# INC-FBTMC429-V1.net
KiCad netlist of a schematic drawn in Altium Designer
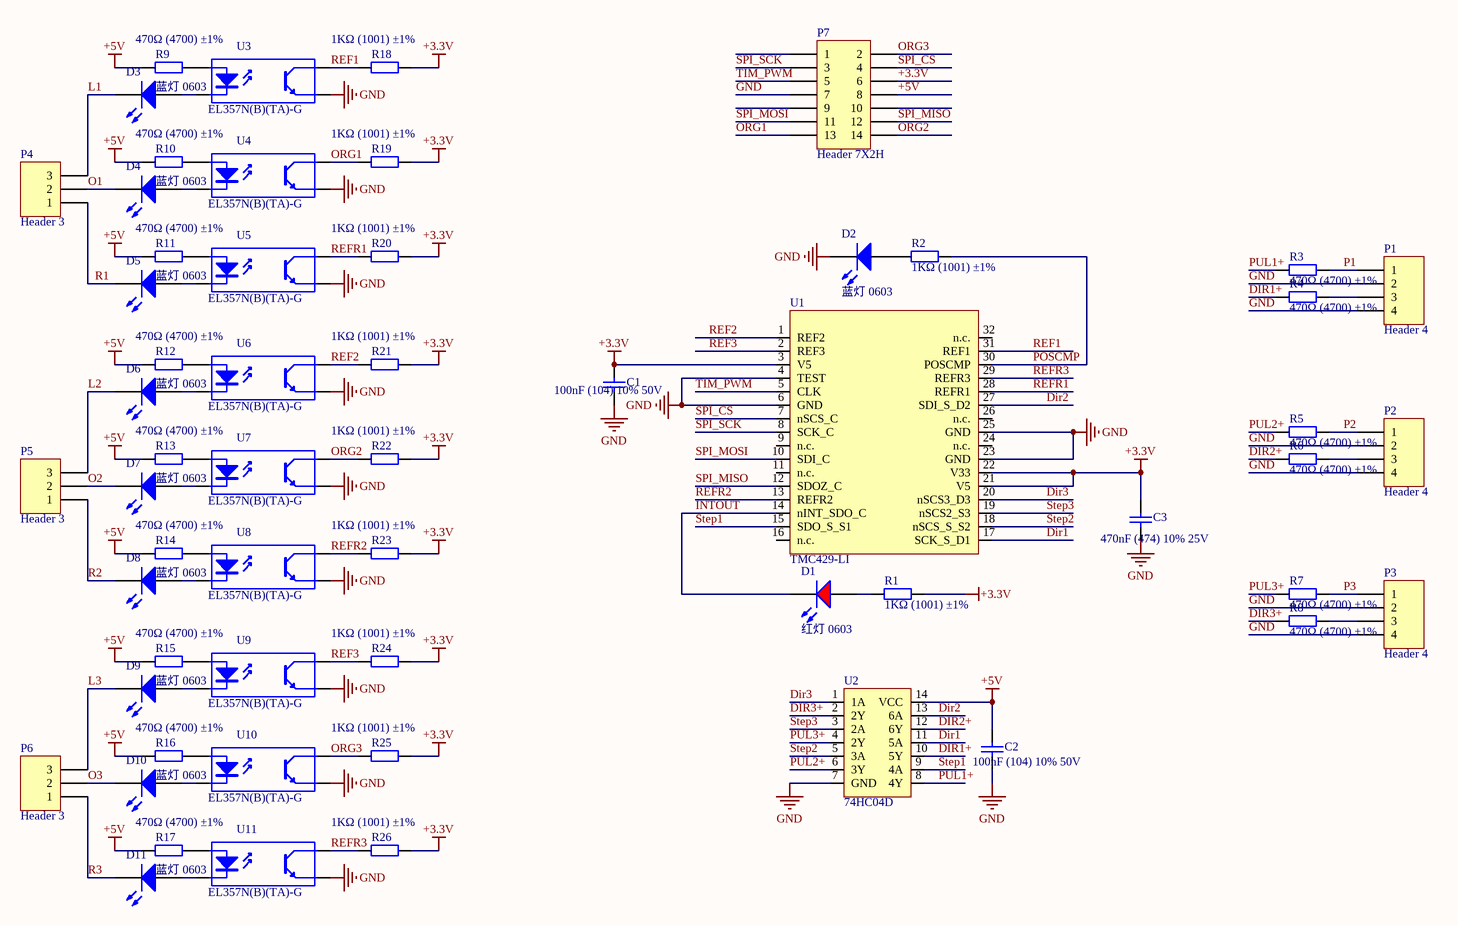
[diagram p0: INC-FBTMC429-V1.SchDoc]

(export (version "E")
  (design (tool "Eeschema 10.0.6"))
  (components
    (comp (ref "C1")
      (value "100nF (104) 10% 50V")
      (footprint "0603_C")
      (description "贴片电容")
      (libsource (lib "Miscellaneous Devices LC") (part "0603 100nF (104) 10% 50V"))
    )
    (comp (ref "C2")
      (value "100nF (104) 10% 50V")
      (footprint "0603_C")
      (description "贴片电容")
      (libsource (lib "Miscellaneous Devices LC") (part "0603 100nF (104) 10% 50V"))
    )
    (comp (ref "C3")
      (value "470nF (474) 10% 25V")
      (footprint "0603_C")
      (description "贴片电容")
      (libsource (lib "Miscellaneous Devices LC") (part "0603 470nF (474) 10% 25V"))
    )
    (comp (ref "D1")
      (value "红灯 0603")
      (footprint "0603_LED_S1")
      (description "发光二极管")
      (libsource (lib "Miscellaneous Devices LC") (part "0603 红灯"))
    )
    (comp (ref "D2")
      (value "蓝灯 0603")
      (footprint "0603_LED_S1")
      (description "发光二极管")
      (libsource (lib "Miscellaneous Devices LC") (part "0603 蓝灯"))
    )
    (comp (ref "D3")
      (value "蓝灯 0603")
      (footprint "0603_LED_S1")
      (description "发光二极管")
      (libsource (lib "Miscellaneous Devices LC") (part "0603 蓝灯"))
    )
    (comp (ref "D4")
      (value "蓝灯 0603")
      (footprint "0603_LED_S1")
      (description "发光二极管")
      (libsource (lib "Miscellaneous Devices LC") (part "0603 蓝灯"))
    )
    (comp (ref "D5")
      (value "蓝灯 0603")
      (footprint "0603_LED_S1")
      (description "发光二极管")
      (libsource (lib "Miscellaneous Devices LC") (part "0603 蓝灯"))
    )
    (comp (ref "D6")
      (value "蓝灯 0603")
      (footprint "0603_LED_S1")
      (description "发光二极管")
      (libsource (lib "Miscellaneous Devices LC") (part "0603 蓝灯"))
    )
    (comp (ref "D7")
      (value "蓝灯 0603")
      (footprint "0603_LED_S1")
      (description "发光二极管")
      (libsource (lib "Miscellaneous Devices LC") (part "0603 蓝灯"))
    )
    (comp (ref "D8")
      (value "蓝灯 0603")
      (footprint "0603_LED_S1")
      (description "发光二极管")
      (libsource (lib "Miscellaneous Devices LC") (part "0603 蓝灯"))
    )
    (comp (ref "D9")
      (value "蓝灯 0603")
      (footprint "0603_LED_S1")
      (description "发光二极管")
      (libsource (lib "Miscellaneous Devices LC") (part "0603 蓝灯"))
    )
    (comp (ref "D10")
      (value "蓝灯 0603")
      (footprint "0603_LED_S1")
      (description "发光二极管")
      (libsource (lib "Miscellaneous Devices LC") (part "0603 蓝灯"))
    )
    (comp (ref "D11")
      (value "蓝灯 0603")
      (footprint "0603_LED_S1")
      (description "发光二极管")
      (libsource (lib "Miscellaneous Devices LC") (part "0603 蓝灯"))
    )
    (comp (ref "P1")
      (value "Header 4")
      (footprint "WJ15EDGVC-3.81-4P")
      (description "Header, 4-Pin")
      (fields (field (name "PUBLISHER") "Altium Limited"))
      (libsource (lib "Miscellaneous Connectors") (part "Header 4"))
    )
    (comp (ref "P2")
      (value "Header 4")
      (footprint "WJ15EDGVC-3.81-4P")
      (description "Header, 4-Pin")
      (fields (field (name "PUBLISHER") "Altium Limited"))
      (libsource (lib "Miscellaneous Connectors") (part "Header 4"))
    )
    (comp (ref "P3")
      (value "Header 4")
      (footprint "WJ15EDGVC-3.81-4P")
      (description "Header, 4-Pin")
      (fields (field (name "PUBLISHER") "Altium Limited"))
      (libsource (lib "Miscellaneous Connectors") (part "Header 4"))
    )
    (comp (ref "P4")
      (value "Header 3")
      (footprint "WJ15EDGVC-3.81-3P")
      (description "Header, 3-Pin")
      (fields (field (name "PUBLISHER") "Altium Limited"))
      (libsource (lib "Miscellaneous Connectors") (part "Header 3"))
    )
    (comp (ref "P5")
      (value "Header 3")
      (footprint "WJ15EDGVC-3.81-3P")
      (description "Header, 3-Pin")
      (fields (field (name "PUBLISHER") "Altium Limited"))
      (libsource (lib "Miscellaneous Connectors") (part "Header 3"))
    )
    (comp (ref "P6")
      (value "Header 3")
      (footprint "WJ15EDGVC-3.81-3P")
      (description "Header, 3-Pin")
      (fields (field (name "PUBLISHER") "Altium Limited"))
      (libsource (lib "Miscellaneous Connectors") (part "Header 3"))
    )
    (comp (ref "P7")
      (value "Header 7X2H")
      (footprint "直牛角连接器 2*7*2.54")
      (description "Header, 7-Pin, Dual row, Right Angle")
      (fields (field (name "PUBLISHER") "Altium Limited"))
      (libsource (lib "Miscellaneous Connectors") (part "Header 7X2H"))
    )
    (comp (ref "R1")
      (value "1KΩ (1001) ±1%")
      (footprint "0603_R")
      (description "贴片电阻")
      (libsource (lib "") (part "0603 1KΩ (1001) 1%_1"))
    )
    (comp (ref "R2")
      (value "1KΩ (1001) ±1%")
      (footprint "0603_R")
      (description "贴片电阻")
      (libsource (lib "") (part "0603 1KΩ (1001) 1%_1"))
    )
    (comp (ref "R3")
      (value "470Ω (4700) ±1%")
      (footprint "0603_R")
      (description "贴片电阻")
      (libsource (lib "Miscellaneous Devices LC") (part "0603 470Ω (4700) 1%"))
    )
    (comp (ref "R4")
      (value "470Ω (4700) ±1%")
      (footprint "0603_R")
      (description "贴片电阻")
      (libsource (lib "Miscellaneous Devices LC") (part "0603 470Ω (4700) 1%"))
    )
    (comp (ref "R5")
      (value "470Ω (4700) ±1%")
      (footprint "0603_R")
      (description "贴片电阻")
      (libsource (lib "Miscellaneous Devices LC") (part "0603 470Ω (4700) 1%"))
    )
    (comp (ref "R6")
      (value "470Ω (4700) ±1%")
      (footprint "0603_R")
      (description "贴片电阻")
      (libsource (lib "Miscellaneous Devices LC") (part "0603 470Ω (4700) 1%"))
    )
    (comp (ref "R7")
      (value "470Ω (4700) ±1%")
      (footprint "0603_R")
      (description "贴片电阻")
      (libsource (lib "Miscellaneous Devices LC") (part "0603 470Ω (4700) 1%"))
    )
    (comp (ref "R8")
      (value "470Ω (4700) ±1%")
      (footprint "0603_R")
      (description "贴片电阻")
      (libsource (lib "Miscellaneous Devices LC") (part "0603 470Ω (4700) 1%"))
    )
    (comp (ref "R9")
      (value "470Ω (4700) ±1%")
      (footprint "0603_R")
      (description "贴片电阻")
      (libsource (lib "Miscellaneous Devices LC") (part "0603 470Ω (4700) 1%"))
    )
    (comp (ref "R10")
      (value "470Ω (4700) ±1%")
      (footprint "0603_R")
      (description "贴片电阻")
      (libsource (lib "Miscellaneous Devices LC") (part "0603 470Ω (4700) 1%"))
    )
    (comp (ref "R11")
      (value "470Ω (4700) ±1%")
      (footprint "0603_R")
      (description "贴片电阻")
      (libsource (lib "Miscellaneous Devices LC") (part "0603 470Ω (4700) 1%"))
    )
    (comp (ref "R12")
      (value "470Ω (4700) ±1%")
      (footprint "0603_R")
      (description "贴片电阻")
      (libsource (lib "Miscellaneous Devices LC") (part "0603 470Ω (4700) 1%"))
    )
    (comp (ref "R13")
      (value "470Ω (4700) ±1%")
      (footprint "0603_R")
      (description "贴片电阻")
      (libsource (lib "Miscellaneous Devices LC") (part "0603 470Ω (4700) 1%"))
    )
    (comp (ref "R14")
      (value "470Ω (4700) ±1%")
      (footprint "0603_R")
      (description "贴片电阻")
      (libsource (lib "Miscellaneous Devices LC") (part "0603 470Ω (4700) 1%"))
    )
    (comp (ref "R15")
      (value "470Ω (4700) ±1%")
      (footprint "0603_R")
      (description "贴片电阻")
      (libsource (lib "Miscellaneous Devices LC") (part "0603 470Ω (4700) 1%"))
    )
    (comp (ref "R16")
      (value "470Ω (4700) ±1%")
      (footprint "0603_R")
      (description "贴片电阻")
      (libsource (lib "Miscellaneous Devices LC") (part "0603 470Ω (4700) 1%"))
    )
    (comp (ref "R17")
      (value "470Ω (4700) ±1%")
      (footprint "0603_R")
      (description "贴片电阻")
      (libsource (lib "Miscellaneous Devices LC") (part "0603 470Ω (4700) 1%"))
    )
    (comp (ref "R18")
      (value "1KΩ (1001) ±1%")
      (footprint "0603_R")
      (description "贴片电阻")
      (libsource (lib "Miscellaneous Devices LC") (part "0603 1KΩ (1001) 1%"))
    )
    (comp (ref "R19")
      (value "1KΩ (1001) ±1%")
      (footprint "0603_R")
      (description "贴片电阻")
      (libsource (lib "Miscellaneous Devices LC") (part "0603 1KΩ (1001) 1%"))
    )
    (comp (ref "R20")
      (value "1KΩ (1001) ±1%")
      (footprint "0603_R")
      (description "贴片电阻")
      (libsource (lib "Miscellaneous Devices LC") (part "0603 1KΩ (1001) 1%"))
    )
    (comp (ref "R21")
      (value "1KΩ (1001) ±1%")
      (footprint "0603_R")
      (description "贴片电阻")
      (libsource (lib "Miscellaneous Devices LC") (part "0603 1KΩ (1001) 1%"))
    )
    (comp (ref "R22")
      (value "1KΩ (1001) ±1%")
      (footprint "0603_R")
      (description "贴片电阻")
      (libsource (lib "Miscellaneous Devices LC") (part "0603 1KΩ (1001) 1%"))
    )
    (comp (ref "R23")
      (value "1KΩ (1001) ±1%")
      (footprint "0603_R")
      (description "贴片电阻")
      (libsource (lib "Miscellaneous Devices LC") (part "0603 1KΩ (1001) 1%"))
    )
    (comp (ref "R24")
      (value "1KΩ (1001) ±1%")
      (footprint "0603_R")
      (description "贴片电阻")
      (libsource (lib "Miscellaneous Devices LC") (part "0603 1KΩ (1001) 1%"))
    )
    (comp (ref "R25")
      (value "1KΩ (1001) ±1%")
      (footprint "0603_R")
      (description "贴片电阻")
      (libsource (lib "Miscellaneous Devices LC") (part "0603 1KΩ (1001) 1%"))
    )
    (comp (ref "R26")
      (value "1KΩ (1001) ±1%")
      (footprint "0603_R")
      (description "贴片电阻")
      (libsource (lib "Miscellaneous Devices LC") (part "0603 1KΩ (1001) 1%"))
    )
    (comp (ref "U1")
      (value "TMC429-LI")
      (footprint "QFN-32_5x5x05P")
      (libsource (lib "GB-SCH") (part "TMC429-LI"))
    )
    (comp (ref "U2")
      (value "74HC04D")
      (footprint "SOIC-14_150mil")
      (libsource (lib "GB-SCH") (part "74HC04"))
    )
    (comp (ref "U3")
      (value "EL357N(B)(TA)-G")
      (footprint "SOP-4_P2.54")
      (description "贴片光耦")
      (libsource (lib "Miscellaneous Devices LC") (part "EL357N(B)(TA)-G"))
    )
    (comp (ref "U4")
      (value "EL357N(B)(TA)-G")
      (footprint "SOP-4_P2.54")
      (description "贴片光耦")
      (libsource (lib "Miscellaneous Devices LC") (part "EL357N(B)(TA)-G"))
    )
    (comp (ref "U5")
      (value "EL357N(B)(TA)-G")
      (footprint "SOP-4_P2.54")
      (description "贴片光耦")
      (libsource (lib "Miscellaneous Devices LC") (part "EL357N(B)(TA)-G"))
    )
    (comp (ref "U6")
      (value "EL357N(B)(TA)-G")
      (footprint "SOP-4_P2.54")
      (description "贴片光耦")
      (libsource (lib "Miscellaneous Devices LC") (part "EL357N(B)(TA)-G"))
    )
    (comp (ref "U7")
      (value "EL357N(B)(TA)-G")
      (footprint "SOP-4_P2.54")
      (description "贴片光耦")
      (libsource (lib "Miscellaneous Devices LC") (part "EL357N(B)(TA)-G"))
    )
    (comp (ref "U8")
      (value "EL357N(B)(TA)-G")
      (footprint "SOP-4_P2.54")
      (description "贴片光耦")
      (libsource (lib "Miscellaneous Devices LC") (part "EL357N(B)(TA)-G"))
    )
    (comp (ref "U9")
      (value "EL357N(B)(TA)-G")
      (footprint "SOP-4_P2.54")
      (description "贴片光耦")
      (libsource (lib "Miscellaneous Devices LC") (part "EL357N(B)(TA)-G"))
    )
    (comp (ref "U10")
      (value "EL357N(B)(TA)-G")
      (footprint "SOP-4_P2.54")
      (description "贴片光耦")
      (libsource (lib "Miscellaneous Devices LC") (part "EL357N(B)(TA)-G"))
    )
    (comp (ref "U11")
      (value "EL357N(B)(TA)-G")
      (footprint "SOP-4_P2.54")
      (description "贴片光耦")
      (libsource (lib "Miscellaneous Devices LC") (part "EL357N(B)(TA)-G"))
    )
  )
  (nets
    (net (code "1") (name "+3.3V") (class "Default")
      (node (ref "C1") (pin "2") (pinfunction "2_2") (pintype "passive"))
      (node (ref "C3") (pin "2") (pinfunction "2_2") (pintype "passive"))
      (node (ref "P7") (pin "6") (pinfunction "6_6") (pintype "passive"))
      (node (ref "R1") (pin "2") (pinfunction "2_2") (pintype "passive"))
      (node (ref "R18") (pin "1") (pinfunction "1_1") (pintype "passive"))
      (node (ref "R19") (pin "1") (pinfunction "1_1") (pintype "passive"))
      (node (ref "R20") (pin "1") (pinfunction "1_1") (pintype "passive"))
      (node (ref "R21") (pin "1") (pinfunction "1_1") (pintype "passive"))
      (node (ref "R22") (pin "1") (pinfunction "1_1") (pintype "passive"))
      (node (ref "R23") (pin "1") (pinfunction "1_1") (pintype "passive"))
      (node (ref "R24") (pin "1") (pinfunction "1_1") (pintype "passive"))
      (node (ref "R25") (pin "1") (pinfunction "1_1") (pintype "passive"))
      (node (ref "R26") (pin "1") (pinfunction "1_1") (pintype "passive"))
      (node (ref "U1") (pin "21") (pinfunction "V5_21") (pintype "passive"))
      (node (ref "U1") (pin "22") (pinfunction "V33_22") (pintype "passive"))
      (node (ref "U1") (pin "3") (pinfunction "V5_3") (pintype "passive"))
    )
    (net (code "2") (name "+5V") (class "Default")
      (node (ref "C2") (pin "1") (pinfunction "1_1") (pintype "passive"))
      (node (ref "P7") (pin "8") (pinfunction "8_8") (pintype "passive"))
      (node (ref "R10") (pin "1") (pinfunction "1_1") (pintype "passive"))
      (node (ref "R11") (pin "1") (pinfunction "1_1") (pintype "passive"))
      (node (ref "R12") (pin "1") (pinfunction "1_1") (pintype "passive"))
      (node (ref "R13") (pin "1") (pinfunction "1_1") (pintype "passive"))
      (node (ref "R14") (pin "1") (pinfunction "1_1") (pintype "passive"))
      (node (ref "R15") (pin "1") (pinfunction "1_1") (pintype "passive"))
      (node (ref "R16") (pin "1") (pinfunction "1_1") (pintype "passive"))
      (node (ref "R17") (pin "1") (pinfunction "1_1") (pintype "passive"))
      (node (ref "R9") (pin "1") (pinfunction "1_1") (pintype "passive"))
      (node (ref "U2") (pin "14") (pinfunction "VCC_14") (pintype "passive"))
    )
    (net (code "3") (name "/DIR1+") (class "Default")
      (node (ref "R4") (pin "1") (pinfunction "1_1") (pintype "passive"))
      (node (ref "U2") (pin "10") (pinfunction "5Y_10") (pintype "passive"))
    )
    (net (code "4") (name "/DIR2+") (class "Default")
      (node (ref "R6") (pin "1") (pinfunction "1_1") (pintype "passive"))
      (node (ref "U2") (pin "12") (pinfunction "6Y_12") (pintype "passive"))
    )
    (net (code "5") (name "/DIR3+") (class "Default")
      (node (ref "R8") (pin "1") (pinfunction "1_1") (pintype "passive"))
      (node (ref "U2") (pin "2") (pinfunction "2Y_2") (pintype "passive"))
    )
    (net (code "6") (name "/Dir1") (class "Default")
      (node (ref "U1") (pin "17") (pinfunction "SCK_S_D1_17") (pintype "passive"))
      (node (ref "U2") (pin "11") (pinfunction "5A_11") (pintype "passive"))
    )
    (net (code "7") (name "/Dir2") (class "Default")
      (node (ref "U1") (pin "27") (pinfunction "SDI_S_D2_27") (pintype "passive"))
      (node (ref "U2") (pin "13") (pinfunction "6A_13") (pintype "passive"))
    )
    (net (code "8") (name "/Dir3") (class "Default")
      (node (ref "U1") (pin "20") (pinfunction "nSCS3_D3_20") (pintype "passive"))
      (node (ref "U2") (pin "1") (pinfunction "1A_1") (pintype "passive"))
    )
    (net (code "9") (name "/INTOUT") (class "Default")
      (node (ref "D1") (pin "K") (pinfunction "K_K") (pintype "passive"))
      (node (ref "U1") (pin "14") (pinfunction "nINT_SDO_C_14") (pintype "passive"))
    )
    (net (code "10") (name "/L1") (class "Default")
      (node (ref "D3") (pin "K") (pinfunction "K_K") (pintype "passive"))
      (node (ref "P4") (pin "3") (pinfunction "3_3") (pintype "passive"))
    )
    (net (code "11") (name "/L2") (class "Default")
      (node (ref "D6") (pin "K") (pinfunction "K_K") (pintype "passive"))
      (node (ref "P5") (pin "3") (pinfunction "3_3") (pintype "passive"))
    )
    (net (code "12") (name "/L3") (class "Default")
      (node (ref "D9") (pin "K") (pinfunction "K_K") (pintype "passive"))
      (node (ref "P6") (pin "3") (pinfunction "3_3") (pintype "passive"))
    )
    (net (code "13") (name "/O1") (class "Default")
      (node (ref "D4") (pin "K") (pinfunction "K_K") (pintype "passive"))
      (node (ref "P4") (pin "2") (pinfunction "2_2") (pintype "passive"))
    )
    (net (code "14") (name "/O2") (class "Default")
      (node (ref "D7") (pin "K") (pinfunction "K_K") (pintype "passive"))
      (node (ref "P5") (pin "2") (pinfunction "2_2") (pintype "passive"))
    )
    (net (code "15") (name "/O3") (class "Default")
      (node (ref "D10") (pin "K") (pinfunction "K_K") (pintype "passive"))
      (node (ref "P6") (pin "2") (pinfunction "2_2") (pintype "passive"))
    )
    (net (code "16") (name "/ORG1") (class "Default")
      (node (ref "P7") (pin "13") (pinfunction "13_13") (pintype "passive"))
      (node (ref "R19") (pin "2") (pinfunction "2_2") (pintype "passive"))
      (node (ref "U4") (pin "4") (pinfunction "C_4") (pintype "passive"))
    )
    (net (code "17") (name "/ORG2") (class "Default")
      (node (ref "P7") (pin "14") (pinfunction "14_14") (pintype "passive"))
      (node (ref "R22") (pin "2") (pinfunction "2_2") (pintype "passive"))
      (node (ref "U7") (pin "4") (pinfunction "C_4") (pintype "passive"))
    )
    (net (code "18") (name "/ORG3") (class "Default")
      (node (ref "P7") (pin "2") (pinfunction "2_2") (pintype "passive"))
      (node (ref "R25") (pin "2") (pinfunction "2_2") (pintype "passive"))
      (node (ref "U10") (pin "4") (pinfunction "C_4") (pintype "passive"))
    )
    (net (code "19") (name "/P1") (class "Default")
      (node (ref "P1") (pin "1") (pinfunction "1_1") (pintype "passive"))
      (node (ref "R3") (pin "2") (pinfunction "2_2") (pintype "passive"))
    )
    (net (code "20") (name "/P2") (class "Default")
      (node (ref "P2") (pin "1") (pinfunction "1_1") (pintype "passive"))
      (node (ref "R5") (pin "2") (pinfunction "2_2") (pintype "passive"))
    )
    (net (code "21") (name "/P3") (class "Default")
      (node (ref "P3") (pin "1") (pinfunction "1_1") (pintype "passive"))
      (node (ref "R7") (pin "2") (pinfunction "2_2") (pintype "passive"))
    )
    (net (code "22") (name "/POSCMP") (class "Default")
      (node (ref "R2") (pin "2") (pinfunction "2_2") (pintype "passive"))
      (node (ref "U1") (pin "30") (pinfunction "POSCMP_30") (pintype "passive"))
    )
    (net (code "23") (name "/PUL1+") (class "Default")
      (node (ref "R3") (pin "1") (pinfunction "1_1") (pintype "passive"))
      (node (ref "U2") (pin "8") (pinfunction "4Y_8") (pintype "passive"))
    )
    (net (code "24") (name "/PUL2+") (class "Default")
      (node (ref "R5") (pin "1") (pinfunction "1_1") (pintype "passive"))
      (node (ref "U2") (pin "6") (pinfunction "3Y_6") (pintype "passive"))
    )
    (net (code "25") (name "/PUL3+") (class "Default")
      (node (ref "R7") (pin "1") (pinfunction "1_1") (pintype "passive"))
      (node (ref "U2") (pin "4") (pinfunction "2Y_4") (pintype "passive"))
    )
    (net (code "26") (name "/R1") (class "Default")
      (node (ref "D5") (pin "K") (pinfunction "K_K") (pintype "passive"))
      (node (ref "P4") (pin "1") (pinfunction "1_1") (pintype "passive"))
    )
    (net (code "27") (name "/R2") (class "Default")
      (node (ref "D8") (pin "K") (pinfunction "K_K") (pintype "passive"))
      (node (ref "P5") (pin "1") (pinfunction "1_1") (pintype "passive"))
    )
    (net (code "28") (name "/R3") (class "Default")
      (node (ref "D11") (pin "K") (pinfunction "K_K") (pintype "passive"))
      (node (ref "P6") (pin "1") (pinfunction "1_1") (pintype "passive"))
    )
    (net (code "29") (name "/REF1") (class "Default")
      (node (ref "R18") (pin "2") (pinfunction "2_2") (pintype "passive"))
      (node (ref "U1") (pin "31") (pinfunction "REF1_31") (pintype "passive"))
      (node (ref "U3") (pin "4") (pinfunction "C_4") (pintype "passive"))
    )
    (net (code "30") (name "/REF2") (class "Default")
      (node (ref "R21") (pin "2") (pinfunction "2_2") (pintype "passive"))
      (node (ref "U1") (pin "1") (pinfunction "REF2_1") (pintype "passive"))
      (node (ref "U6") (pin "4") (pinfunction "C_4") (pintype "passive"))
    )
    (net (code "31") (name "/REF3") (class "Default")
      (node (ref "R24") (pin "2") (pinfunction "2_2") (pintype "passive"))
      (node (ref "U1") (pin "2") (pinfunction "REF3_2") (pintype "passive"))
      (node (ref "U9") (pin "4") (pinfunction "C_4") (pintype "passive"))
    )
    (net (code "32") (name "/REFR1") (class "Default")
      (node (ref "R20") (pin "2") (pinfunction "2_2") (pintype "passive"))
      (node (ref "U1") (pin "28") (pinfunction "REFR1_28") (pintype "passive"))
      (node (ref "U5") (pin "4") (pinfunction "C_4") (pintype "passive"))
    )
    (net (code "33") (name "/REFR2") (class "Default")
      (node (ref "R23") (pin "2") (pinfunction "2_2") (pintype "passive"))
      (node (ref "U1") (pin "13") (pinfunction "REFR2_13") (pintype "passive"))
      (node (ref "U8") (pin "4") (pinfunction "C_4") (pintype "passive"))
    )
    (net (code "34") (name "/REFR3") (class "Default")
      (node (ref "R26") (pin "2") (pinfunction "2_2") (pintype "passive"))
      (node (ref "U1") (pin "29") (pinfunction "REFR3_29") (pintype "passive"))
      (node (ref "U11") (pin "4") (pinfunction "C_4") (pintype "passive"))
    )
    (net (code "35") (name "/SPI_CS") (class "Default")
      (node (ref "P7") (pin "4") (pinfunction "4_4") (pintype "passive"))
      (node (ref "U1") (pin "7") (pinfunction "nSCS_C_7") (pintype "passive"))
    )
    (net (code "36") (name "/SPI_MISO") (class "Default")
      (node (ref "P7") (pin "12") (pinfunction "12_12") (pintype "passive"))
      (node (ref "U1") (pin "12") (pinfunction "SDOZ_C_12") (pintype "passive"))
    )
    (net (code "37") (name "/SPI_MOSI") (class "Default")
      (node (ref "P7") (pin "11") (pinfunction "11_11") (pintype "passive"))
      (node (ref "U1") (pin "10") (pinfunction "SDI_C_10") (pintype "passive"))
    )
    (net (code "38") (name "/SPI_SCK") (class "Default")
      (node (ref "P7") (pin "3") (pinfunction "3_3") (pintype "passive"))
      (node (ref "U1") (pin "8") (pinfunction "SCK_C_8") (pintype "passive"))
    )
    (net (code "39") (name "/Step1") (class "Default")
      (node (ref "U1") (pin "15") (pinfunction "SDO_S_S1_15") (pintype "passive"))
      (node (ref "U2") (pin "9") (pinfunction "4A_9") (pintype "passive"))
    )
    (net (code "40") (name "/Step2") (class "Default")
      (node (ref "U1") (pin "18") (pinfunction "nSCS_S_S2_18") (pintype "passive"))
      (node (ref "U2") (pin "5") (pinfunction "3A_5") (pintype "passive"))
    )
    (net (code "41") (name "/Step3") (class "Default")
      (node (ref "U1") (pin "19") (pinfunction "nSCS2_S3_19") (pintype "passive"))
      (node (ref "U2") (pin "3") (pinfunction "2A_3") (pintype "passive"))
    )
    (net (code "42") (name "/TIM_PWM") (class "Default")
      (node (ref "P7") (pin "5") (pinfunction "5_5") (pintype "passive"))
      (node (ref "U1") (pin "5") (pinfunction "CLK_5") (pintype "passive"))
    )
    (net (code "43") (name "GND") (class "Default")
      (node (ref "C1") (pin "1") (pinfunction "1_1") (pintype "passive"))
      (node (ref "C2") (pin "2") (pinfunction "2_2") (pintype "passive"))
      (node (ref "C3") (pin "1") (pinfunction "1_1") (pintype "passive"))
      (node (ref "D2") (pin "K") (pinfunction "K_K") (pintype "passive"))
      (node (ref "P1") (pin "2") (pinfunction "2_2") (pintype "passive"))
      (node (ref "P1") (pin "4") (pinfunction "4_4") (pintype "passive"))
      (node (ref "P2") (pin "2") (pinfunction "2_2") (pintype "passive"))
      (node (ref "P2") (pin "4") (pinfunction "4_4") (pintype "passive"))
      (node (ref "P3") (pin "2") (pinfunction "2_2") (pintype "passive"))
      (node (ref "P3") (pin "4") (pinfunction "4_4") (pintype "passive"))
      (node (ref "P7") (pin "7") (pinfunction "7_7") (pintype "passive"))
      (node (ref "U1") (pin "23") (pinfunction "GND_23") (pintype "passive"))
      (node (ref "U1") (pin "25") (pinfunction "GND_25") (pintype "passive"))
      (node (ref "U1") (pin "4") (pinfunction "TEST_4") (pintype "passive"))
      (node (ref "U1") (pin "6") (pinfunction "GND_6") (pintype "passive"))
      (node (ref "U10") (pin "3") (pinfunction "E_3") (pintype "passive"))
      (node (ref "U11") (pin "3") (pinfunction "E_3") (pintype "passive"))
      (node (ref "U2") (pin "7") (pinfunction "GND_7") (pintype "passive"))
      (node (ref "U3") (pin "3") (pinfunction "E_3") (pintype "passive"))
      (node (ref "U4") (pin "3") (pinfunction "E_3") (pintype "passive"))
      (node (ref "U5") (pin "3") (pinfunction "E_3") (pintype "passive"))
      (node (ref "U6") (pin "3") (pinfunction "E_3") (pintype "passive"))
      (node (ref "U7") (pin "3") (pinfunction "E_3") (pintype "passive"))
      (node (ref "U8") (pin "3") (pinfunction "E_3") (pintype "passive"))
      (node (ref "U9") (pin "3") (pinfunction "E_3") (pintype "passive"))
    )
    (net (code "44") (name "Net-(D1-PadA)") (class "Default")
      (node (ref "D1") (pin "A") (pinfunction "A_A") (pintype "passive"))
      (node (ref "R1") (pin "1") (pinfunction "1_1") (pintype "passive"))
    )
    (net (code "45") (name "Net-(D2-PadA)") (class "Default")
      (node (ref "D2") (pin "A") (pinfunction "A_A") (pintype "passive"))
      (node (ref "R2") (pin "1") (pinfunction "1_1") (pintype "passive"))
    )
    (net (code "46") (name "Net-(P1-Pad3)") (class "Default")
      (node (ref "P1") (pin "3") (pinfunction "3_3") (pintype "passive"))
      (node (ref "R4") (pin "2") (pinfunction "2_2") (pintype "passive"))
    )
    (net (code "47") (name "Net-(P2-Pad3)") (class "Default")
      (node (ref "P2") (pin "3") (pinfunction "3_3") (pintype "passive"))
      (node (ref "R6") (pin "2") (pinfunction "2_2") (pintype "passive"))
    )
    (net (code "48") (name "Net-(P3-Pad3)") (class "Default")
      (node (ref "P3") (pin "3") (pinfunction "3_3") (pintype "passive"))
      (node (ref "R8") (pin "2") (pinfunction "2_2") (pintype "passive"))
    )
    (net (code "49") (name "Net-(U3-A)") (class "Default")
      (node (ref "R9") (pin "2") (pinfunction "2_2") (pintype "passive"))
      (node (ref "U3") (pin "1") (pinfunction "A_1") (pintype "passive"))
    )
    (net (code "50") (name "Net-(U3-K)") (class "Default")
      (node (ref "D3") (pin "A") (pinfunction "A_A") (pintype "passive"))
      (node (ref "U3") (pin "2") (pinfunction "K_2") (pintype "passive"))
    )
    (net (code "51") (name "Net-(U4-A)") (class "Default")
      (node (ref "R10") (pin "2") (pinfunction "2_2") (pintype "passive"))
      (node (ref "U4") (pin "1") (pinfunction "A_1") (pintype "passive"))
    )
    (net (code "52") (name "Net-(U4-K)") (class "Default")
      (node (ref "D4") (pin "A") (pinfunction "A_A") (pintype "passive"))
      (node (ref "U4") (pin "2") (pinfunction "K_2") (pintype "passive"))
    )
    (net (code "53") (name "Net-(U5-A)") (class "Default")
      (node (ref "R11") (pin "2") (pinfunction "2_2") (pintype "passive"))
      (node (ref "U5") (pin "1") (pinfunction "A_1") (pintype "passive"))
    )
    (net (code "54") (name "Net-(U5-K)") (class "Default")
      (node (ref "D5") (pin "A") (pinfunction "A_A") (pintype "passive"))
      (node (ref "U5") (pin "2") (pinfunction "K_2") (pintype "passive"))
    )
    (net (code "55") (name "Net-(U6-A)") (class "Default")
      (node (ref "R12") (pin "2") (pinfunction "2_2") (pintype "passive"))
      (node (ref "U6") (pin "1") (pinfunction "A_1") (pintype "passive"))
    )
    (net (code "56") (name "Net-(U6-K)") (class "Default")
      (node (ref "D6") (pin "A") (pinfunction "A_A") (pintype "passive"))
      (node (ref "U6") (pin "2") (pinfunction "K_2") (pintype "passive"))
    )
    (net (code "57") (name "Net-(U7-A)") (class "Default")
      (node (ref "R13") (pin "2") (pinfunction "2_2") (pintype "passive"))
      (node (ref "U7") (pin "1") (pinfunction "A_1") (pintype "passive"))
    )
    (net (code "58") (name "Net-(U7-K)") (class "Default")
      (node (ref "D7") (pin "A") (pinfunction "A_A") (pintype "passive"))
      (node (ref "U7") (pin "2") (pinfunction "K_2") (pintype "passive"))
    )
    (net (code "59") (name "Net-(U8-A)") (class "Default")
      (node (ref "R14") (pin "2") (pinfunction "2_2") (pintype "passive"))
      (node (ref "U8") (pin "1") (pinfunction "A_1") (pintype "passive"))
    )
    (net (code "60") (name "Net-(U8-K)") (class "Default")
      (node (ref "D8") (pin "A") (pinfunction "A_A") (pintype "passive"))
      (node (ref "U8") (pin "2") (pinfunction "K_2") (pintype "passive"))
    )
    (net (code "61") (name "Net-(U9-A)") (class "Default")
      (node (ref "R15") (pin "2") (pinfunction "2_2") (pintype "passive"))
      (node (ref "U9") (pin "1") (pinfunction "A_1") (pintype "passive"))
    )
    (net (code "62") (name "Net-(U9-K)") (class "Default")
      (node (ref "D9") (pin "A") (pinfunction "A_A") (pintype "passive"))
      (node (ref "U9") (pin "2") (pinfunction "K_2") (pintype "passive"))
    )
    (net (code "63") (name "Net-(U10-A)") (class "Default")
      (node (ref "R16") (pin "2") (pinfunction "2_2") (pintype "passive"))
      (node (ref "U10") (pin "1") (pinfunction "A_1") (pintype "passive"))
    )
    (net (code "64") (name "Net-(U10-K)") (class "Default")
      (node (ref "D10") (pin "A") (pinfunction "A_A") (pintype "passive"))
      (node (ref "U10") (pin "2") (pinfunction "K_2") (pintype "passive"))
    )
    (net (code "65") (name "Net-(U11-A)") (class "Default")
      (node (ref "R17") (pin "2") (pinfunction "2_2") (pintype "passive"))
      (node (ref "U11") (pin "1") (pinfunction "A_1") (pintype "passive"))
    )
    (net (code "66") (name "Net-(U11-K)") (class "Default")
      (node (ref "D11") (pin "A") (pinfunction "A_A") (pintype "passive"))
      (node (ref "U11") (pin "2") (pinfunction "K_2") (pintype "passive"))
    )
    (net (code "67") (name "unconnected-(P7-Pad1)") (class "Default")
      (node (ref "P7") (pin "1") (pinfunction "1_1") (pintype "passive"))
    )
    (net (code "68") (name "unconnected-(P7-Pad9)") (class "Default")
      (node (ref "P7") (pin "9") (pinfunction "9_9") (pintype "passive"))
    )
    (net (code "69") (name "unconnected-(P7-Pad10)") (class "Default")
      (node (ref "P7") (pin "10") (pinfunction "10_10") (pintype "passive"))
    )
    (net (code "70") (name "unconnected-(U1-n.c.-Pad9)") (class "Default")
      (node (ref "U1") (pin "9") (pinfunction "n.c._9") (pintype "passive"))
    )
    (net (code "71") (name "unconnected-(U1-n.c.-Pad11)") (class "Default")
      (node (ref "U1") (pin "11") (pinfunction "n.c._11") (pintype "passive"))
    )
    (net (code "72") (name "unconnected-(U1-n.c.-Pad16)") (class "Default")
      (node (ref "U1") (pin "16") (pinfunction "n.c._16") (pintype "passive"))
    )
    (net (code "73") (name "unconnected-(U1-n.c.-Pad24)") (class "Default")
      (node (ref "U1") (pin "24") (pinfunction "n.c._24") (pintype "passive"))
    )
    (net (code "74") (name "unconnected-(U1-n.c.-Pad26)") (class "Default")
      (node (ref "U1") (pin "26") (pinfunction "n.c._26") (pintype "passive"))
    )
    (net (code "75") (name "unconnected-(U1-n.c.-Pad32)") (class "Default")
      (node (ref "U1") (pin "32") (pinfunction "n.c._32") (pintype "passive"))
    )
  )
)
